# IOs.net
KiCad netlist of a schematic drawn in Altium Designer
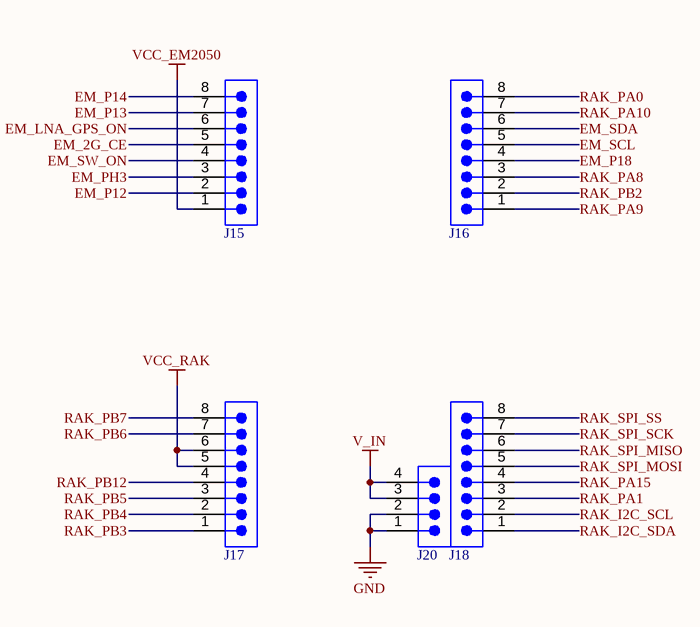
[diagram p0: IOs.SchDoc]

(export (version "E")
  (design (tool "Eeschema 10.0.6"))
  (components
    (comp (ref "J15")
      (value "61300811121")
      (footprint "61300811121")
      (libsource (lib "ApolloEcho_Dev_Kit") (part "Header_Male_1R_08P"))
    )
    (comp (ref "J16")
      (value "61300811121")
      (footprint "61300811121")
      (libsource (lib "ApolloEcho_Dev_Kit") (part "Header_Male_1R_08P"))
    )
    (comp (ref "J17")
      (value "61300811121")
      (footprint "61300811121")
      (libsource (lib "ApolloEcho_Dev_Kit") (part "Header_Male_1R_08P"))
    )
    (comp (ref "J18")
      (value "61300811121")
      (footprint "61300811121")
      (libsource (lib "ApolloEcho_Dev_Kit") (part "Header_Male_1R_08P"))
    )
    (comp (ref "J20")
      (value "61300411121")
      (footprint "61300411121")
      (libsource (lib "ApolloEcho_Dev_Kit") (part "Header_Male_1R_04P"))
    )
  )
  (nets
    (net (code "1") (name "/EM_2G_CE") (class "Default")
      (node (ref "J15") (pin "5") (pinfunction "5_5") (pintype "passive"))
    )
    (net (code "2") (name "/EM_LNA_GPS_ON") (class "Default")
      (node (ref "J15") (pin "6") (pinfunction "6_6") (pintype "passive"))
    )
    (net (code "3") (name "/EM_P12") (class "Default")
      (node (ref "J15") (pin "2") (pinfunction "2_2") (pintype "passive"))
    )
    (net (code "4") (name "/EM_P13") (class "Default")
      (node (ref "J15") (pin "7") (pinfunction "7_7") (pintype "passive"))
    )
    (net (code "5") (name "/EM_P14") (class "Default")
      (node (ref "J15") (pin "8") (pinfunction "8_8") (pintype "passive"))
    )
    (net (code "6") (name "/EM_P18") (class "Default")
      (node (ref "J16") (pin "4") (pinfunction "4_4") (pintype "passive"))
    )
    (net (code "7") (name "/EM_PH3") (class "Default")
      (node (ref "J15") (pin "3") (pinfunction "3_3") (pintype "passive"))
    )
    (net (code "8") (name "/EM_SCL") (class "Default")
      (node (ref "J16") (pin "5") (pinfunction "5_5") (pintype "passive"))
    )
    (net (code "9") (name "/EM_SDA") (class "Default")
      (node (ref "J16") (pin "6") (pinfunction "6_6") (pintype "passive"))
    )
    (net (code "10") (name "/EM_SW_ON") (class "Default")
      (node (ref "J15") (pin "4") (pinfunction "4_4") (pintype "passive"))
    )
    (net (code "11") (name "/RAK_I2C_SCL") (class "Default")
      (node (ref "J18") (pin "2") (pinfunction "2_2") (pintype "passive"))
    )
    (net (code "12") (name "/RAK_I2C_SDA") (class "Default")
      (node (ref "J18") (pin "1") (pinfunction "1_1") (pintype "passive"))
    )
    (net (code "13") (name "/RAK_PA0") (class "Default")
      (node (ref "J16") (pin "8") (pinfunction "8_8") (pintype "passive"))
    )
    (net (code "14") (name "/RAK_PA1") (class "Default")
      (node (ref "J18") (pin "3") (pinfunction "3_3") (pintype "passive"))
    )
    (net (code "15") (name "/RAK_PA8") (class "Default")
      (node (ref "J16") (pin "3") (pinfunction "3_3") (pintype "passive"))
    )
    (net (code "16") (name "/RAK_PA9") (class "Default")
      (node (ref "J16") (pin "1") (pinfunction "1_1") (pintype "passive"))
    )
    (net (code "17") (name "/RAK_PA10") (class "Default")
      (node (ref "J16") (pin "7") (pinfunction "7_7") (pintype "passive"))
    )
    (net (code "18") (name "/RAK_PA15") (class "Default")
      (node (ref "J18") (pin "4") (pinfunction "4_4") (pintype "passive"))
    )
    (net (code "19") (name "/RAK_PB2") (class "Default")
      (node (ref "J16") (pin "2") (pinfunction "2_2") (pintype "passive"))
    )
    (net (code "20") (name "/RAK_PB3") (class "Default")
      (node (ref "J17") (pin "1") (pinfunction "1_1") (pintype "passive"))
    )
    (net (code "21") (name "/RAK_PB4") (class "Default")
      (node (ref "J17") (pin "2") (pinfunction "2_2") (pintype "passive"))
    )
    (net (code "22") (name "/RAK_PB5") (class "Default")
      (node (ref "J17") (pin "3") (pinfunction "3_3") (pintype "passive"))
    )
    (net (code "23") (name "/RAK_PB6") (class "Default")
      (node (ref "J17") (pin "7") (pinfunction "7_7") (pintype "passive"))
    )
    (net (code "24") (name "/RAK_PB7") (class "Default")
      (node (ref "J17") (pin "8") (pinfunction "8_8") (pintype "passive"))
    )
    (net (code "25") (name "/RAK_PB12") (class "Default")
      (node (ref "J17") (pin "4") (pinfunction "4_4") (pintype "passive"))
    )
    (net (code "26") (name "/RAK_SPI_MISO") (class "Default")
      (node (ref "J18") (pin "6") (pinfunction "6_6") (pintype "passive"))
    )
    (net (code "27") (name "/RAK_SPI_MOSI") (class "Default")
      (node (ref "J18") (pin "5") (pinfunction "5_5") (pintype "passive"))
    )
    (net (code "28") (name "/RAK_SPI_SCK") (class "Default")
      (node (ref "J18") (pin "7") (pinfunction "7_7") (pintype "passive"))
    )
    (net (code "29") (name "/RAK_SPI_SS") (class "Default")
      (node (ref "J18") (pin "8") (pinfunction "8_8") (pintype "passive"))
    )
    (net (code "30") (name "GND") (class "Default")
      (node (ref "J20") (pin "1") (pinfunction "1_1") (pintype "passive"))
      (node (ref "J20") (pin "2") (pinfunction "2_2") (pintype "passive"))
    )
    (net (code "31") (name "VCC_EM2050") (class "Default")
      (node (ref "J15") (pin "1") (pinfunction "1_1") (pintype "passive"))
    )
    (net (code "32") (name "VCC_RAK") (class "Default")
      (node (ref "J17") (pin "5") (pinfunction "5_5") (pintype "passive"))
      (node (ref "J17") (pin "6") (pinfunction "6_6") (pintype "passive"))
    )
    (net (code "33") (name "V_IN") (class "Default")
      (node (ref "J20") (pin "3") (pinfunction "3_3") (pintype "passive"))
      (node (ref "J20") (pin "4") (pinfunction "4_4") (pintype "passive"))
    )
  )
)
